# G879.net
KiCad netlist of a schematic drawn in EAGLE
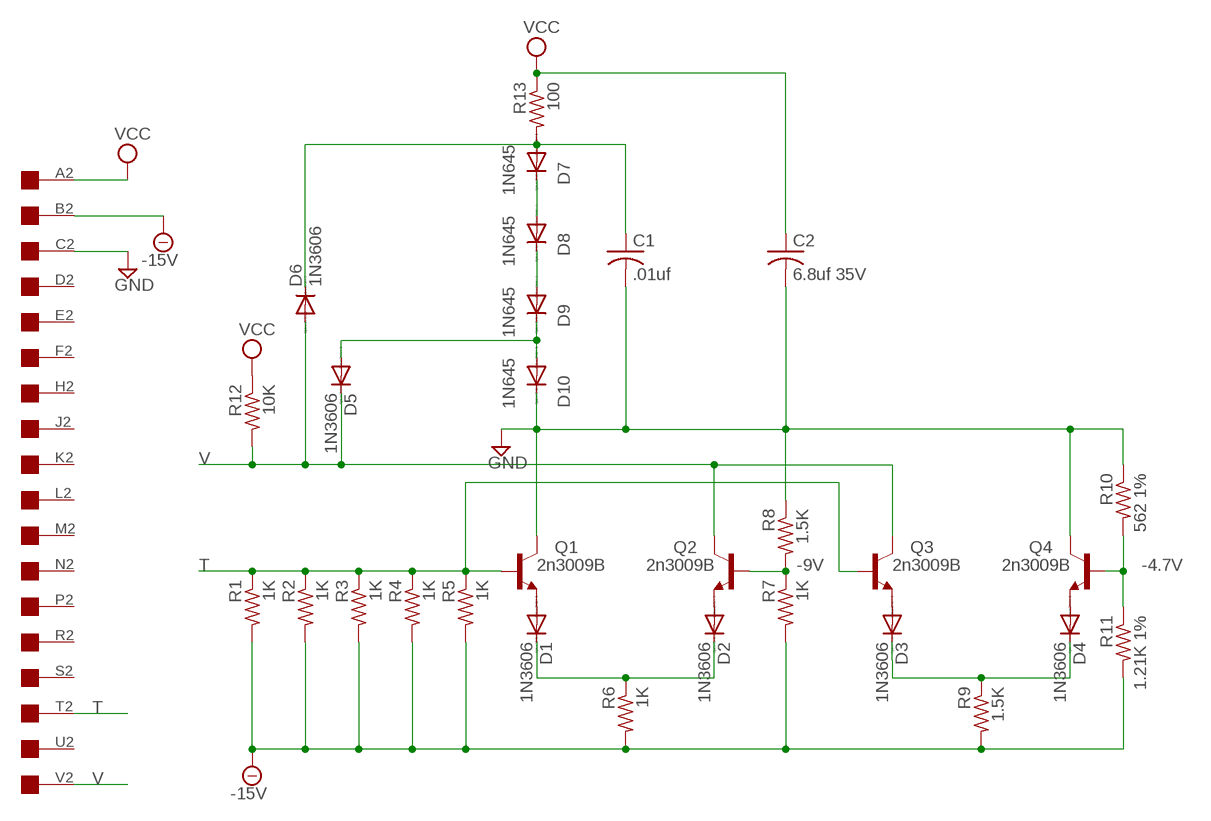
[diagram p0: schematic, sheet 1]

(export (version "E")
  (design (tool "Eeschema 10.0.6"))
  (components
    (comp (ref "C1")
      (value ".01uf")
      (footprint "eagle-import:C050-025X075")
      (libsource (lib "eagle-import") (part "C-US050-025X075"))
    )
    (comp (ref "C2")
      (value "6.8uf 35V")
      (footprint "eagle-import:C102-054X133")
      (libsource (lib "eagle-import") (part "C-US102-054X133"))
    )
    (comp (ref "D1")
      (value "1N3606")
      (footprint "eagle-import:DO41-10")
      (libsource (lib "eagle-import") (part "1N4004"))
    )
    (comp (ref "D2")
      (value "1N3606")
      (footprint "eagle-import:DO41-10")
      (libsource (lib "eagle-import") (part "1N4004"))
    )
    (comp (ref "D3")
      (value "1N3606")
      (footprint "eagle-import:DO41-10")
      (libsource (lib "eagle-import") (part "1N4004"))
    )
    (comp (ref "D4")
      (value "1N3606")
      (footprint "eagle-import:DO41-10")
      (libsource (lib "eagle-import") (part "1N4004"))
    )
    (comp (ref "D5")
      (value "1N3606")
      (footprint "eagle-import:DO41-10")
      (libsource (lib "eagle-import") (part "1N4004"))
    )
    (comp (ref "D6")
      (value "1N3606")
      (footprint "eagle-import:DO41-10")
      (libsource (lib "eagle-import") (part "1N4004"))
    )
    (comp (ref "D7")
      (value "1N645")
      (footprint "eagle-import:DO41-10")
      (libsource (lib "eagle-import") (part "1N4004"))
    )
    (comp (ref "D8")
      (value "1N645")
      (footprint "eagle-import:DO41-10")
      (libsource (lib "eagle-import") (part "1N4004"))
    )
    (comp (ref "D9")
      (value "1N645")
      (footprint "eagle-import:DO41-10")
      (libsource (lib "eagle-import") (part "1N4004"))
    )
    (comp (ref "D10")
      (value "1N645")
      (footprint "eagle-import:DO41-10")
      (libsource (lib "eagle-import") (part "1N4004"))
    )
    (comp (ref "Q1")
      (value "2n3009B")
      (footprint "eagle-import:TO39")
      (libsource (lib "eagle-import") (part "2N1711"))
    )
    (comp (ref "Q2")
      (value "2n3009B")
      (footprint "eagle-import:TO39")
      (libsource (lib "eagle-import") (part "2N1711"))
    )
    (comp (ref "Q3")
      (value "2n3009B")
      (footprint "eagle-import:TO39")
      (libsource (lib "eagle-import") (part "2N1711"))
    )
    (comp (ref "Q4")
      (value "2n3009B")
      (footprint "eagle-import:TO39")
      (libsource (lib "eagle-import") (part "2N1711"))
    )
    (comp (ref "R1")
      (value "1K")
      (footprint "eagle-import:0207_10")
      (libsource (lib "eagle-import") (part "R-US_0207/10"))
    )
    (comp (ref "R2")
      (value "1K")
      (footprint "eagle-import:0207_10")
      (libsource (lib "eagle-import") (part "R-US_0207/10"))
    )
    (comp (ref "R3")
      (value "1K")
      (footprint "eagle-import:0207_10")
      (libsource (lib "eagle-import") (part "R-US_0207/10"))
    )
    (comp (ref "R4")
      (value "1K")
      (footprint "eagle-import:0207_10")
      (libsource (lib "eagle-import") (part "R-US_0207/10"))
    )
    (comp (ref "R5")
      (value "1K")
      (footprint "eagle-import:0207_10")
      (libsource (lib "eagle-import") (part "R-US_0207/10"))
    )
    (comp (ref "R6")
      (value "1K")
      (footprint "eagle-import:0207_10")
      (libsource (lib "eagle-import") (part "R-US_0207/10"))
    )
    (comp (ref "R7")
      (value "1K")
      (footprint "eagle-import:0207_10")
      (libsource (lib "eagle-import") (part "R-US_0207/10"))
    )
    (comp (ref "R8")
      (value "1.5K")
      (footprint "eagle-import:0207_10")
      (libsource (lib "eagle-import") (part "R-US_0207/10"))
    )
    (comp (ref "R9")
      (value "1.5K")
      (footprint "eagle-import:0207_10")
      (libsource (lib "eagle-import") (part "R-US_0207/10"))
    )
    (comp (ref "R10")
      (value "562 1%")
      (footprint "eagle-import:0207_10")
      (libsource (lib "eagle-import") (part "R-US_0207/10"))
    )
    (comp (ref "R11")
      (value "1.21K 1%")
      (footprint "eagle-import:0207_10")
      (libsource (lib "eagle-import") (part "R-US_0207/10"))
    )
    (comp (ref "R12")
      (value "10K")
      (footprint "eagle-import:0207_10")
      (libsource (lib "eagle-import") (part "R-US_0207/10"))
    )
    (comp (ref "R13")
      (value "100")
      (footprint "eagle-import:0207_10")
      (libsource (lib "eagle-import") (part "R-US_0207/10"))
    )
    (comp (ref "U$5")
      (value "ONE-SIDED")
      (footprint "eagle-import:ONE-SIDED")
      (libsource (lib "eagle-import") (part "ONE-SIDED"))
    )
  )
  (nets
    (net (code "1") (name "-15V") (class "Default")
      (node (ref "R1") (pin "2") (pinfunction "2_2") (pintype "passive"))
      (node (ref "R11") (pin "2") (pinfunction "2_2") (pintype "passive"))
      (node (ref "R2") (pin "2") (pinfunction "2_2") (pintype "passive"))
      (node (ref "R3") (pin "2") (pinfunction "2_2") (pintype "passive"))
      (node (ref "R4") (pin "2") (pinfunction "2_2") (pintype "passive"))
      (node (ref "R5") (pin "2") (pinfunction "2_2") (pintype "passive"))
      (node (ref "R6") (pin "2") (pinfunction "2_2") (pintype "passive"))
      (node (ref "R7") (pin "2") (pinfunction "2_2") (pintype "passive"))
      (node (ref "R9") (pin "2") (pinfunction "2_2") (pintype "passive"))
      (node (ref "U$5") (pin "B2") (pinfunction "B2_B2") (pintype "passive"))
    )
    (net (code "2") (name "/-4.7V") (class "Default")
      (node (ref "Q4") (pin "2") (pinfunction "B_2") (pintype "passive"))
      (node (ref "R10") (pin "2") (pinfunction "2_2") (pintype "passive"))
      (node (ref "R11") (pin "1") (pinfunction "1_1") (pintype "passive"))
    )
    (net (code "3") (name "/-9V") (class "Default")
      (node (ref "Q2") (pin "2") (pinfunction "B_2") (pintype "passive"))
      (node (ref "R7") (pin "1") (pinfunction "1_1") (pintype "passive"))
      (node (ref "R8") (pin "2") (pinfunction "2_2") (pintype "passive"))
    )
    (net (code "4") (name "/T") (class "Default")
      (node (ref "Q1") (pin "2") (pinfunction "B_2") (pintype "passive"))
      (node (ref "Q3") (pin "2") (pinfunction "B_2") (pintype "passive"))
      (node (ref "R1") (pin "1") (pinfunction "1_1") (pintype "passive"))
      (node (ref "R2") (pin "1") (pinfunction "1_1") (pintype "passive"))
      (node (ref "R3") (pin "1") (pinfunction "1_1") (pintype "passive"))
      (node (ref "R4") (pin "1") (pinfunction "1_1") (pintype "passive"))
      (node (ref "R5") (pin "1") (pinfunction "1_1") (pintype "passive"))
      (node (ref "U$5") (pin "T2") (pinfunction "T2_T2") (pintype "passive"))
    )
    (net (code "5") (name "/V") (class "Default")
      (node (ref "D5") (pin "C") (pinfunction "C_C") (pintype "passive"))
      (node (ref "D6") (pin "A") (pinfunction "A_A") (pintype "passive"))
      (node (ref "Q2") (pin "3") (pinfunction "C_3") (pintype "passive"))
      (node (ref "Q3") (pin "3") (pinfunction "C_3") (pintype "passive"))
      (node (ref "R12") (pin "2") (pinfunction "2_2") (pintype "passive"))
      (node (ref "U$5") (pin "V2") (pinfunction "V2_V2") (pintype "passive"))
    )
    (net (code "6") (name "GND") (class "Default")
      (node (ref "C1") (pin "2") (pinfunction "2_2") (pintype "passive"))
      (node (ref "C2") (pin "2") (pinfunction "2_2") (pintype "passive"))
      (node (ref "D10") (pin "C") (pinfunction "C_C") (pintype "passive"))
      (node (ref "Q1") (pin "3") (pinfunction "C_3") (pintype "passive"))
      (node (ref "Q4") (pin "3") (pinfunction "C_3") (pintype "passive"))
      (node (ref "R10") (pin "1") (pinfunction "1_1") (pintype "passive"))
      (node (ref "R8") (pin "1") (pinfunction "1_1") (pintype "passive"))
      (node (ref "U$5") (pin "C2") (pinfunction "C2_C2") (pintype "passive"))
    )
    (net (code "7") (name "Net-(C1-Pad1)") (class "Default")
      (node (ref "C1") (pin "1") (pinfunction "1_1") (pintype "passive"))
      (node (ref "D6") (pin "C") (pinfunction "C_C") (pintype "passive"))
      (node (ref "D7") (pin "A") (pinfunction "A_A") (pintype "passive"))
      (node (ref "R13") (pin "2") (pinfunction "2_2") (pintype "passive"))
    )
    (net (code "8") (name "Net-(D1-PadC)") (class "Default")
      (node (ref "D1") (pin "C") (pinfunction "C_C") (pintype "passive"))
      (node (ref "D2") (pin "C") (pinfunction "C_C") (pintype "passive"))
      (node (ref "R6") (pin "1") (pinfunction "1_1") (pintype "passive"))
    )
    (net (code "9") (name "Net-(D3-PadC)") (class "Default")
      (node (ref "D3") (pin "C") (pinfunction "C_C") (pintype "passive"))
      (node (ref "D4") (pin "C") (pinfunction "C_C") (pintype "passive"))
      (node (ref "R9") (pin "1") (pinfunction "1_1") (pintype "passive"))
    )
    (net (code "10") (name "Net-(D7-PadC)") (class "Default")
      (node (ref "D7") (pin "C") (pinfunction "C_C") (pintype "passive"))
      (node (ref "D8") (pin "A") (pinfunction "A_A") (pintype "passive"))
    )
    (net (code "11") (name "Net-(D8-PadC)") (class "Default")
      (node (ref "D8") (pin "C") (pinfunction "C_C") (pintype "passive"))
      (node (ref "D9") (pin "A") (pinfunction "A_A") (pintype "passive"))
    )
    (net (code "12") (name "Net-(D10-PadA)") (class "Default")
      (node (ref "D10") (pin "A") (pinfunction "A_A") (pintype "passive"))
      (node (ref "D5") (pin "A") (pinfunction "A_A") (pintype "passive"))
      (node (ref "D9") (pin "C") (pinfunction "C_C") (pintype "passive"))
    )
    (net (code "13") (name "Net-(Q1-E)") (class "Default")
      (node (ref "D1") (pin "A") (pinfunction "A_A") (pintype "passive"))
      (node (ref "Q1") (pin "1") (pinfunction "E_1") (pintype "passive"))
    )
    (net (code "14") (name "Net-(Q2-E)") (class "Default")
      (node (ref "D2") (pin "A") (pinfunction "A_A") (pintype "passive"))
      (node (ref "Q2") (pin "1") (pinfunction "E_1") (pintype "passive"))
    )
    (net (code "15") (name "Net-(Q3-E)") (class "Default")
      (node (ref "D3") (pin "A") (pinfunction "A_A") (pintype "passive"))
      (node (ref "Q3") (pin "1") (pinfunction "E_1") (pintype "passive"))
    )
    (net (code "16") (name "Net-(Q4-E)") (class "Default")
      (node (ref "D4") (pin "A") (pinfunction "A_A") (pintype "passive"))
      (node (ref "Q4") (pin "1") (pinfunction "E_1") (pintype "passive"))
    )
    (net (code "17") (name "VCC") (class "Default")
      (node (ref "C2") (pin "1") (pinfunction "1_1") (pintype "passive"))
      (node (ref "R12") (pin "1") (pinfunction "1_1") (pintype "passive"))
      (node (ref "R13") (pin "1") (pinfunction "1_1") (pintype "passive"))
      (node (ref "U$5") (pin "A2") (pinfunction "A2_A2") (pintype "passive"))
    )
    (net (code "18") (name "unconnected-(U$5-PadD2)") (class "Default")
      (node (ref "U$5") (pin "D2") (pinfunction "D2_D2") (pintype "passive"))
    )
    (net (code "19") (name "unconnected-(U$5-PadE2)") (class "Default")
      (node (ref "U$5") (pin "E2") (pinfunction "E2_E2") (pintype "passive"))
    )
    (net (code "20") (name "unconnected-(U$5-PadF2)") (class "Default")
      (node (ref "U$5") (pin "F2") (pinfunction "F2_F2") (pintype "passive"))
    )
    (net (code "21") (name "unconnected-(U$5-PadH2)") (class "Default")
      (node (ref "U$5") (pin "H2") (pinfunction "H2_H2") (pintype "passive"))
    )
    (net (code "22") (name "unconnected-(U$5-PadJ2)") (class "Default")
      (node (ref "U$5") (pin "J2") (pinfunction "J2_J2") (pintype "passive"))
    )
    (net (code "23") (name "unconnected-(U$5-PadK2)") (class "Default")
      (node (ref "U$5") (pin "K2") (pinfunction "K2_K2") (pintype "passive"))
    )
    (net (code "24") (name "unconnected-(U$5-PadL2)") (class "Default")
      (node (ref "U$5") (pin "L2") (pinfunction "L2_L2") (pintype "passive"))
    )
    (net (code "25") (name "unconnected-(U$5-PadM2)") (class "Default")
      (node (ref "U$5") (pin "M2") (pinfunction "M2_M2") (pintype "passive"))
    )
    (net (code "26") (name "unconnected-(U$5-PadN2)") (class "Default")
      (node (ref "U$5") (pin "N2") (pinfunction "N2_N2") (pintype "passive"))
    )
    (net (code "27") (name "unconnected-(U$5-PadP2)") (class "Default")
      (node (ref "U$5") (pin "P2") (pinfunction "P2_P2") (pintype "passive"))
    )
    (net (code "28") (name "unconnected-(U$5-PadR2)") (class "Default")
      (node (ref "U$5") (pin "R2") (pinfunction "R2_R2") (pintype "passive"))
    )
    (net (code "29") (name "unconnected-(U$5-PadS2)") (class "Default")
      (node (ref "U$5") (pin "S2") (pinfunction "S2_S2") (pintype "passive"))
    )
    (net (code "30") (name "unconnected-(U$5-PadU2)") (class "Default")
      (node (ref "U$5") (pin "U2") (pinfunction "U2_U2") (pintype "passive"))
    )
  )
)
